# cpu2_lock.net
KiCad netlist of a schematic drawn in Altium Designer
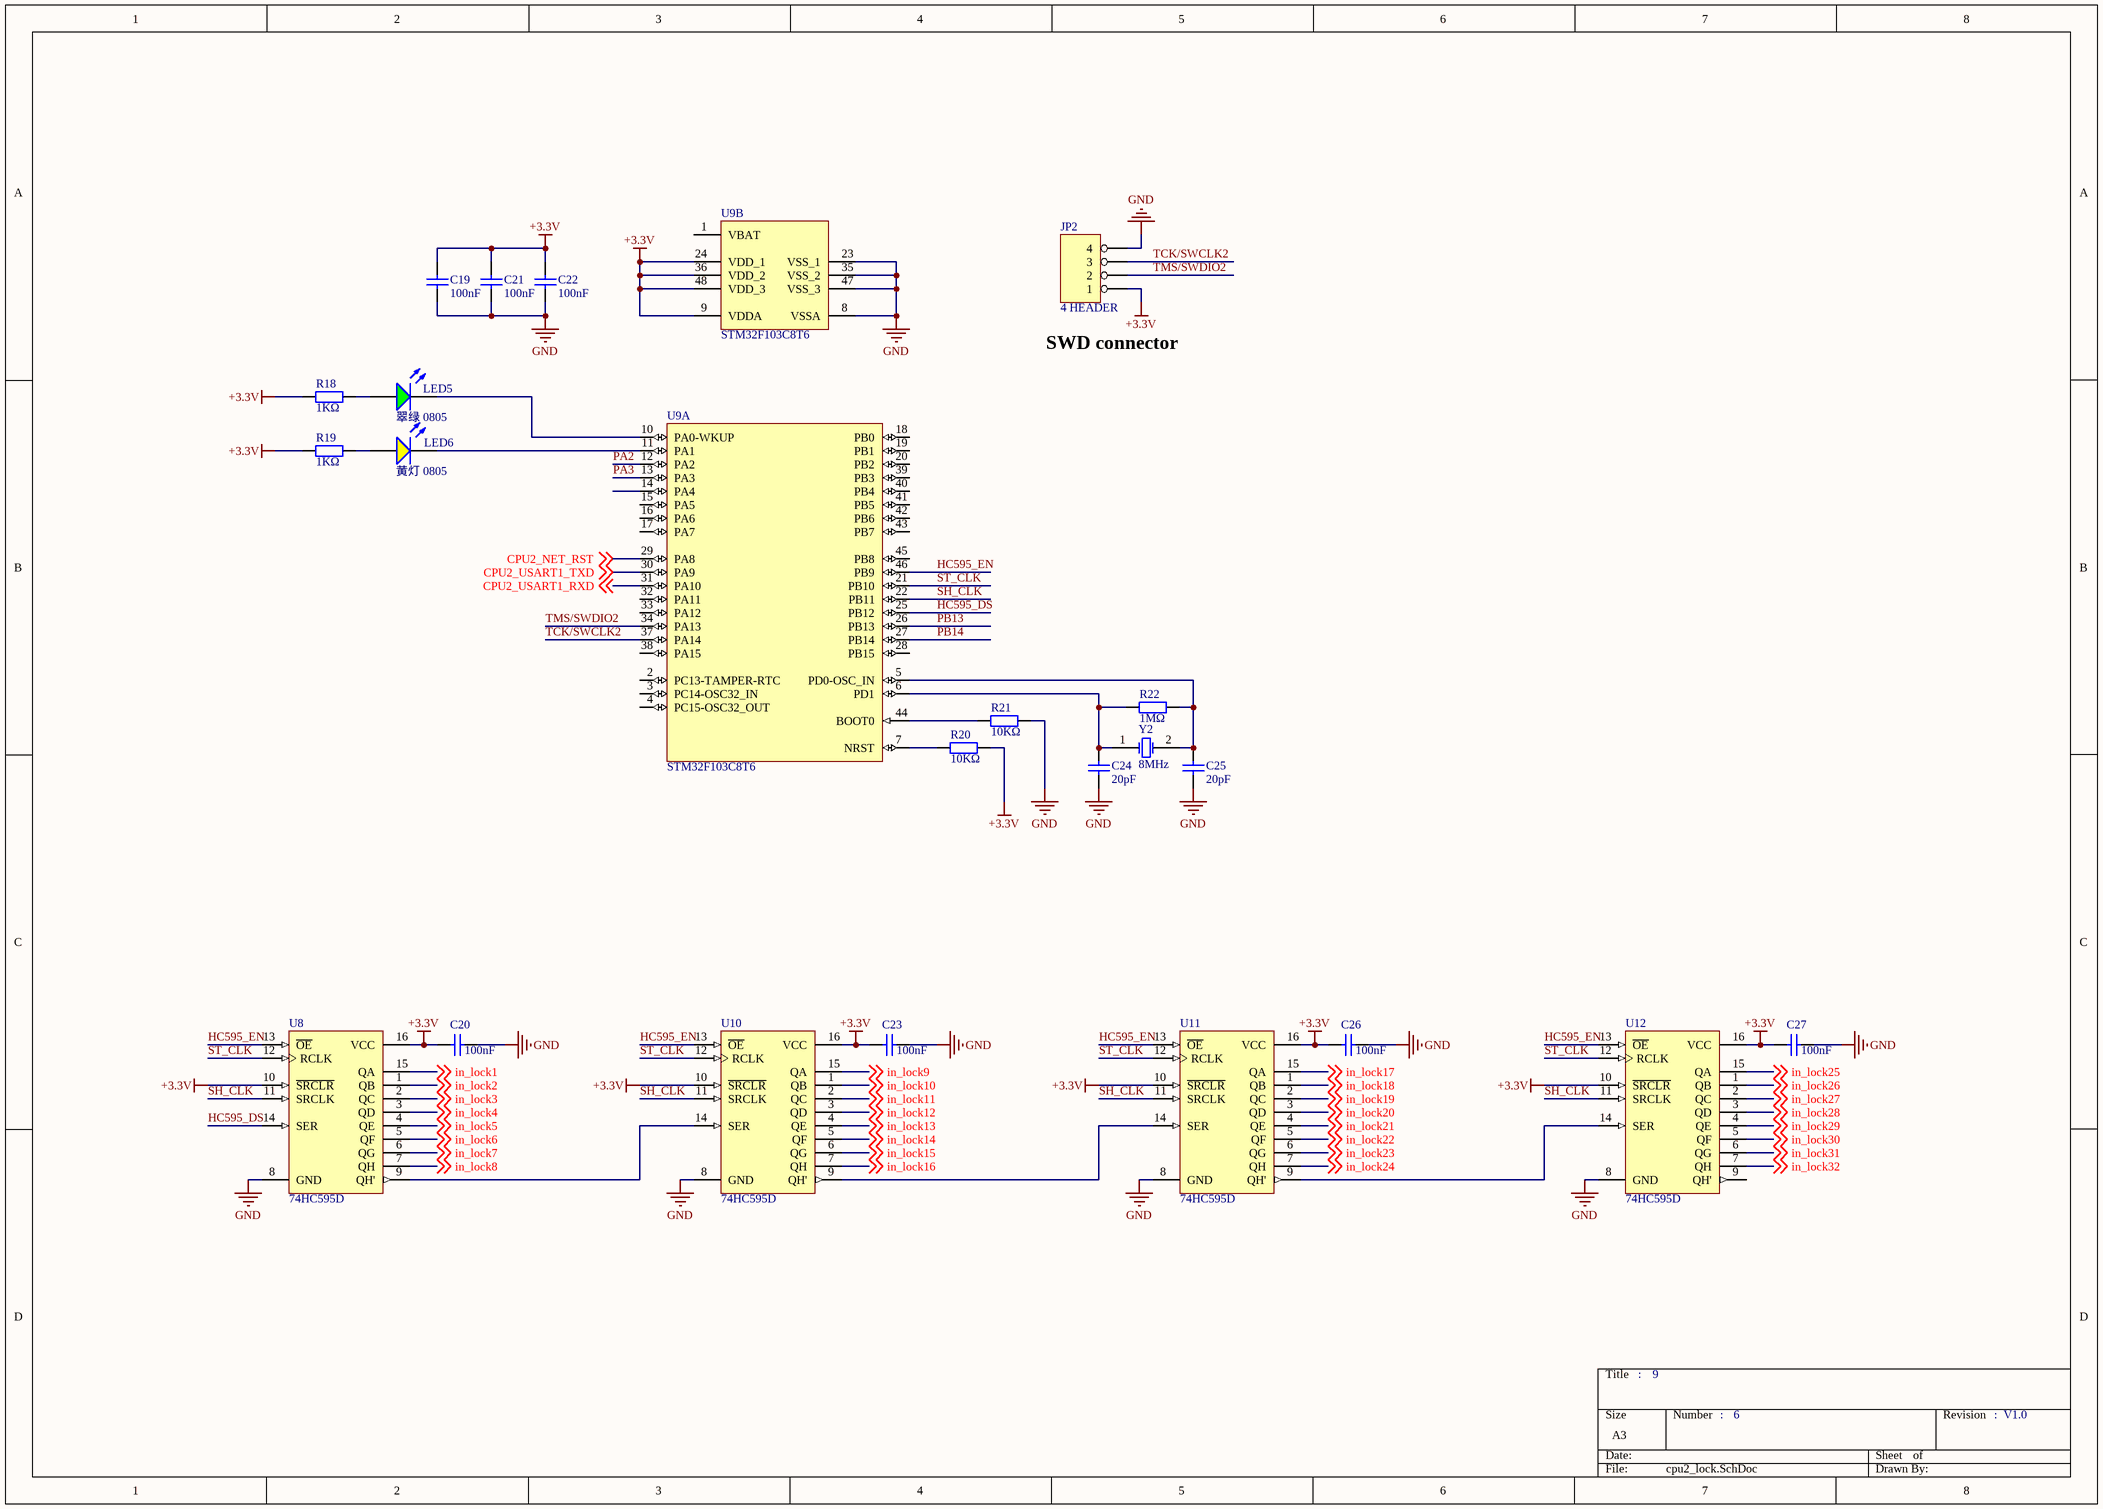
[diagram p0: cpu2_lock.SchDoc]

(export (version "E")
  (design (tool "Eeschema 10.0.6"))
  (components
    (comp (ref "C19")
      (value "100nF")
      (footprint "0805_C")
      (description "贴片电容")
      (libsource (lib "Miscellaneous Devices LC") (part "0805 100nF(104) 10% 50V"))
    )
    (comp (ref "C20")
      (value "100nF")
      (footprint "0805_C")
      (description "贴片电容")
      (libsource (lib "Miscellaneous Devices LC") (part "0805 100nF(104) 10% 50V"))
    )
    (comp (ref "C21")
      (value "100nF")
      (footprint "0805_C")
      (description "贴片电容")
      (libsource (lib "Miscellaneous Devices LC") (part "0805 100nF(104) 10% 50V"))
    )
    (comp (ref "C22")
      (value "100nF")
      (footprint "0805_C")
      (description "贴片电容")
      (libsource (lib "Miscellaneous Devices LC") (part "0805 100nF(104) 10% 50V"))
    )
    (comp (ref "C23")
      (value "100nF")
      (footprint "0805_C")
      (description "贴片电容")
      (libsource (lib "Miscellaneous Devices LC") (part "0805 100nF(104) 10% 50V"))
    )
    (comp (ref "C24")
      (value "20pF")
      (footprint "0805_C")
      (description "贴片电容")
      (libsource (lib "Miscellaneous Devices LC") (part "0805 100nF(104) 10% 50V"))
    )
    (comp (ref "C25")
      (value "20pF")
      (footprint "0805_C")
      (description "贴片电容")
      (libsource (lib "Miscellaneous Devices LC") (part "0805 100nF(104) 10% 50V"))
    )
    (comp (ref "C26")
      (value "100nF")
      (footprint "0805_C")
      (description "贴片电容")
      (libsource (lib "Miscellaneous Devices LC") (part "0805 100nF(104) 10% 50V"))
    )
    (comp (ref "C27")
      (value "100nF")
      (footprint "0805_C")
      (description "贴片电容")
      (libsource (lib "Miscellaneous Devices LC") (part "0805 100nF(104) 10% 50V"))
    )
    (comp (ref "JP2")
      (value "4 HEADER")
      (footprint "CON4_1.5")
      (description "4 Pin Header")
      (libsource (lib "Miscellaneous Devices") (part "4 HEADER"))
    )
    (comp (ref "LED5")
      (value "翠绿 0805")
      (footprint "0805_LED_S1")
      (description "发光二极管")
      (libsource (lib "Miscellaneous Devices LC") (part "0805 翠绿"))
    )
    (comp (ref "LED6")
      (value "黄灯 0805")
      (footprint "0805_LED_S1")
      (description "发光二极管")
      (libsource (lib "Miscellaneous Devices LC") (part "0805 黄灯"))
    )
    (comp (ref "R18")
      (value "1KΩ")
      (footprint "0805_R")
      (description "贴片电阻")
      (libsource (lib "Miscellaneous Devices LC") (part "0805 11KΩ (1102) 1%"))
    )
    (comp (ref "R19")
      (value "1KΩ")
      (footprint "0805_R")
      (description "贴片电阻")
      (libsource (lib "Miscellaneous Devices LC") (part "0805 11KΩ (1102) 1%"))
    )
    (comp (ref "R20")
      (value "10KΩ")
      (footprint "0805_R")
      (description "贴片电阻")
      (libsource (lib "") (part "0805 11KΩ (1102) 1%_1"))
    )
    (comp (ref "R21")
      (value "10KΩ")
      (footprint "0805_R")
      (description "贴片电阻")
      (libsource (lib "") (part "0805 11KΩ (1102) 1%_1"))
    )
    (comp (ref "R22")
      (value "1MΩ")
      (footprint "0805_R")
      (description "贴片电阻")
      (libsource (lib "") (part "0805 11KΩ (1102) 1%_1"))
    )
    (comp (ref "U8")
      (value "74HC595D")
      (footprint "SOIC-16_150mil")
      (description "74系列逻辑芯片")
      (libsource (lib "Miscellaneous Devices LC") (part "74HC595D"))
    )
    (comp (ref "U9")
      (value "STM32F103C8T6")
      (footprint "LQFP-48_7x7x05P")
      (description "ARM")
      (libsource (lib "Miscellaneous Devices LC") (part "STM32F103C8T6"))
    )
    (comp (ref "U10")
      (value "74HC595D")
      (footprint "SOIC-16_150mil")
      (description "74系列逻辑芯片")
      (libsource (lib "Miscellaneous Devices LC") (part "74HC595D"))
    )
    (comp (ref "U11")
      (value "74HC595D")
      (footprint "SOIC-16_150mil")
      (description "74系列逻辑芯片")
      (libsource (lib "Miscellaneous Devices LC") (part "74HC595D"))
    )
    (comp (ref "U12")
      (value "74HC595D")
      (footprint "SOIC-16_150mil")
      (description "74系列逻辑芯片")
      (libsource (lib "Miscellaneous Devices LC") (part "74HC595D"))
    )
    (comp (ref "Y2")
      (value "8MHz")
      (footprint "XTAL_US1")
      (description "Crystal Oscillator")
      (fields (field (name "PUBLISHER") "Altium Limited"))
      (libsource (lib "战舰STM32开发板底板封装库") (part "XTAL"))
    )
  )
  (nets
    (net (code "1") (name "+3.3V") (class "Default")
      (node (ref "C19") (pin "2") (pinfunction "2_2") (pintype "passive"))
      (node (ref "C20") (pin "2") (pinfunction "2_2") (pintype "passive"))
      (node (ref "C21") (pin "2") (pinfunction "2_2") (pintype "passive"))
      (node (ref "C22") (pin "2") (pinfunction "2_2") (pintype "passive"))
      (node (ref "C23") (pin "2") (pinfunction "2_2") (pintype "passive"))
      (node (ref "C26") (pin "2") (pinfunction "2_2") (pintype "passive"))
      (node (ref "C27") (pin "2") (pinfunction "2_2") (pintype "passive"))
      (node (ref "JP2") (pin "1") (pinfunction "1_1") (pintype "passive"))
      (node (ref "R18") (pin "1") (pinfunction "1_1") (pintype "passive"))
      (node (ref "R19") (pin "1") (pinfunction "1_1") (pintype "passive"))
      (node (ref "R20") (pin "1") (pinfunction "1_1") (pintype "passive"))
      (node (ref "U10") (pin "10") (pinfunction "~{SRCLR}_10") (pintype "input"))
      (node (ref "U10") (pin "16") (pinfunction "VCC_16") (pintype "power_in"))
      (node (ref "U11") (pin "10") (pinfunction "~{SRCLR}_10") (pintype "input"))
      (node (ref "U11") (pin "16") (pinfunction "VCC_16") (pintype "power_in"))
      (node (ref "U12") (pin "10") (pinfunction "~{SRCLR}_10") (pintype "input"))
      (node (ref "U12") (pin "16") (pinfunction "VCC_16") (pintype "power_in"))
      (node (ref "U8") (pin "10") (pinfunction "~{SRCLR}_10") (pintype "input"))
      (node (ref "U8") (pin "16") (pinfunction "VCC_16") (pintype "power_in"))
      (node (ref "U9") (pin "24") (pinfunction "VDD_1_24") (pintype "power_in"))
      (node (ref "U9") (pin "36") (pinfunction "VDD_2_36") (pintype "power_in"))
      (node (ref "U9") (pin "48") (pinfunction "VDD_3_48") (pintype "power_in"))
      (node (ref "U9") (pin "9") (pinfunction "VDDA_9") (pintype "power_in"))
    )
    (net (code "2") (name "/HC595_DS") (class "Default")
      (node (ref "U8") (pin "14") (pinfunction "SER_14") (pintype "input"))
      (node (ref "U9") (pin "25") (pinfunction "PB12_25") (pintype "bidirectional"))
    )
    (net (code "3") (name "/HC595_EN") (class "Default")
      (node (ref "U10") (pin "13") (pinfunction "~{OE}_13") (pintype "input"))
      (node (ref "U11") (pin "13") (pinfunction "~{OE}_13") (pintype "input"))
      (node (ref "U12") (pin "13") (pinfunction "~{OE}_13") (pintype "input"))
      (node (ref "U8") (pin "13") (pinfunction "~{OE}_13") (pintype "input"))
      (node (ref "U9") (pin "46") (pinfunction "PB9_46") (pintype "bidirectional"))
    )
    (net (code "4") (name "/PA2") (class "Default")
      (node (ref "U9") (pin "12") (pinfunction "PA2_12") (pintype "bidirectional"))
    )
    (net (code "5") (name "/PA3") (class "Default")
      (node (ref "U9") (pin "13") (pinfunction "PA3_13") (pintype "bidirectional"))
    )
    (net (code "6") (name "/PB13") (class "Default")
      (node (ref "U9") (pin "26") (pinfunction "PB13_26") (pintype "bidirectional"))
    )
    (net (code "7") (name "/PB14") (class "Default")
      (node (ref "U9") (pin "27") (pinfunction "PB14_27") (pintype "bidirectional"))
    )
    (net (code "8") (name "/SH_CLK") (class "Default")
      (node (ref "U10") (pin "11") (pinfunction "SRCLK_11") (pintype "input"))
      (node (ref "U11") (pin "11") (pinfunction "SRCLK_11") (pintype "input"))
      (node (ref "U12") (pin "11") (pinfunction "SRCLK_11") (pintype "input"))
      (node (ref "U8") (pin "11") (pinfunction "SRCLK_11") (pintype "input"))
      (node (ref "U9") (pin "22") (pinfunction "PB11_22") (pintype "bidirectional"))
    )
    (net (code "9") (name "/ST_CLK") (class "Default")
      (node (ref "U10") (pin "12") (pinfunction "RCLK_12") (pintype "input"))
      (node (ref "U11") (pin "12") (pinfunction "RCLK_12") (pintype "input"))
      (node (ref "U12") (pin "12") (pinfunction "RCLK_12") (pintype "input"))
      (node (ref "U8") (pin "12") (pinfunction "RCLK_12") (pintype "input"))
      (node (ref "U9") (pin "21") (pinfunction "PB10_21") (pintype "bidirectional"))
    )
    (net (code "10") (name "/TCK{slash}SWCLK2") (class "Default")
      (node (ref "JP2") (pin "3") (pinfunction "3_3") (pintype "passive"))
      (node (ref "U9") (pin "37") (pinfunction "PA14_37") (pintype "bidirectional"))
    )
    (net (code "11") (name "/TMS{slash}SWDIO2") (class "Default")
      (node (ref "JP2") (pin "2") (pinfunction "2_2") (pintype "passive"))
      (node (ref "U9") (pin "34") (pinfunction "PA13_34") (pintype "bidirectional"))
    )
    (net (code "12") (name "CPU2_NET_RST") (class "Default")
      (node (ref "U9") (pin "29") (pinfunction "PA8_29") (pintype "bidirectional"))
    )
    (net (code "13") (name "CPU2_USART1_RXD") (class "Default")
      (node (ref "U9") (pin "31") (pinfunction "PA10_31") (pintype "bidirectional"))
    )
    (net (code "14") (name "CPU2_USART1_TXD") (class "Default")
      (node (ref "U9") (pin "30") (pinfunction "PA9_30") (pintype "bidirectional"))
    )
    (net (code "15") (name "GND") (class "Default")
      (node (ref "C19") (pin "1") (pinfunction "1_1") (pintype "passive"))
      (node (ref "C20") (pin "1") (pinfunction "1_1") (pintype "passive"))
      (node (ref "C21") (pin "1") (pinfunction "1_1") (pintype "passive"))
      (node (ref "C22") (pin "1") (pinfunction "1_1") (pintype "passive"))
      (node (ref "C23") (pin "1") (pinfunction "1_1") (pintype "passive"))
      (node (ref "C24") (pin "1") (pinfunction "1_1") (pintype "passive"))
      (node (ref "C25") (pin "1") (pinfunction "1_1") (pintype "passive"))
      (node (ref "C26") (pin "1") (pinfunction "1_1") (pintype "passive"))
      (node (ref "C27") (pin "1") (pinfunction "1_1") (pintype "passive"))
      (node (ref "JP2") (pin "4") (pinfunction "4_4") (pintype "passive"))
      (node (ref "R21") (pin "1") (pinfunction "1_1") (pintype "passive"))
      (node (ref "U10") (pin "8") (pinfunction "GND_8") (pintype "power_in"))
      (node (ref "U11") (pin "8") (pinfunction "GND_8") (pintype "power_in"))
      (node (ref "U12") (pin "8") (pinfunction "GND_8") (pintype "power_in"))
      (node (ref "U8") (pin "8") (pinfunction "GND_8") (pintype "power_in"))
      (node (ref "U9") (pin "23") (pinfunction "VSS_1_23") (pintype "power_in"))
      (node (ref "U9") (pin "35") (pinfunction "VSS_2_35") (pintype "power_in"))
      (node (ref "U9") (pin "47") (pinfunction "VSS_3_47") (pintype "power_in"))
      (node (ref "U9") (pin "8") (pinfunction "VSSA_8") (pintype "power_in"))
    )
    (net (code "16") (name "Net-(LED5-PadA)") (class "Default")
      (node (ref "LED5") (pin "A") (pinfunction "A_A") (pintype "passive"))
      (node (ref "R18") (pin "2") (pinfunction "2_2") (pintype "passive"))
    )
    (net (code "17") (name "Net-(LED6-PadA)") (class "Default")
      (node (ref "LED6") (pin "A") (pinfunction "A_A") (pintype "passive"))
      (node (ref "R19") (pin "2") (pinfunction "2_2") (pintype "passive"))
    )
    (net (code "18") (name "Net-(U9A-BOOT0)") (class "Default")
      (node (ref "R21") (pin "2") (pinfunction "2_2") (pintype "passive"))
      (node (ref "U9") (pin "44") (pinfunction "BOOT0_44") (pintype "input"))
    )
    (net (code "19") (name "Net-(U9A-NRST)") (class "Default")
      (node (ref "R20") (pin "2") (pinfunction "2_2") (pintype "passive"))
      (node (ref "U9") (pin "7") (pinfunction "NRST_7") (pintype "bidirectional"))
    )
    (net (code "20") (name "Net-(U9A-PA0-WKUP)") (class "Default")
      (node (ref "LED5") (pin "K") (pinfunction "K_K") (pintype "passive"))
      (node (ref "U9") (pin "10") (pinfunction "PA0-WKUP_10") (pintype "bidirectional"))
    )
    (net (code "21") (name "Net-(U9A-PA1)") (class "Default")
      (node (ref "LED6") (pin "K") (pinfunction "K_K") (pintype "passive"))
      (node (ref "U9") (pin "11") (pinfunction "PA1_11") (pintype "bidirectional"))
    )
    (net (code "22") (name "Net-(U9A-PD0-OSC_IN)") (class "Default")
      (node (ref "C25") (pin "2") (pinfunction "2_2") (pintype "passive"))
      (node (ref "R22") (pin "1") (pinfunction "1_1") (pintype "passive"))
      (node (ref "U9") (pin "5") (pinfunction "PD0-OSC_IN_5") (pintype "bidirectional"))
      (node (ref "Y2") (pin "2") (pinfunction "OSC2_2") (pintype "passive"))
    )
    (net (code "23") (name "Net-(U9A-PD1)") (class "Default")
      (node (ref "C24") (pin "2") (pinfunction "2_2") (pintype "passive"))
      (node (ref "R22") (pin "2") (pinfunction "2_2") (pintype "passive"))
      (node (ref "U9") (pin "6") (pinfunction "PD1_6") (pintype "bidirectional"))
      (node (ref "Y2") (pin "1") (pinfunction "OSC1_1") (pintype "passive"))
    )
    (net (code "24") (name "Net-(U10-QH')") (class "Default")
      (node (ref "U10") (pin "9") (pinfunction "QH'_9") (pintype "output"))
      (node (ref "U11") (pin "14") (pinfunction "SER_14") (pintype "input"))
    )
    (net (code "25") (name "Net-(U10-SER)") (class "Default")
      (node (ref "U10") (pin "14") (pinfunction "SER_14") (pintype "input"))
      (node (ref "U8") (pin "9") (pinfunction "QH'_9") (pintype "output"))
    )
    (net (code "26") (name "Net-(U11-QH')") (class "Default")
      (node (ref "U11") (pin "9") (pinfunction "QH'_9") (pintype "output"))
      (node (ref "U12") (pin "14") (pinfunction "SER_14") (pintype "input"))
    )
    (net (code "27") (name "in_lock1") (class "Default")
      (node (ref "U8") (pin "15") (pinfunction "QA_15") (pintype "tri_state"))
    )
    (net (code "28") (name "in_lock2") (class "Default")
      (node (ref "U8") (pin "1") (pinfunction "QB_1") (pintype "tri_state"))
    )
    (net (code "29") (name "in_lock3") (class "Default")
      (node (ref "U8") (pin "2") (pinfunction "QC_2") (pintype "tri_state"))
    )
    (net (code "30") (name "in_lock4") (class "Default")
      (node (ref "U8") (pin "3") (pinfunction "QD_3") (pintype "tri_state"))
    )
    (net (code "31") (name "in_lock5") (class "Default")
      (node (ref "U8") (pin "4") (pinfunction "QE_4") (pintype "tri_state"))
    )
    (net (code "32") (name "in_lock6") (class "Default")
      (node (ref "U8") (pin "5") (pinfunction "QF_5") (pintype "tri_state"))
    )
    (net (code "33") (name "in_lock7") (class "Default")
      (node (ref "U8") (pin "6") (pinfunction "QG_6") (pintype "tri_state"))
    )
    (net (code "34") (name "in_lock8") (class "Default")
      (node (ref "U8") (pin "7") (pinfunction "QH_7") (pintype "tri_state"))
    )
    (net (code "35") (name "in_lock9") (class "Default")
      (node (ref "U10") (pin "15") (pinfunction "QA_15") (pintype "tri_state"))
    )
    (net (code "36") (name "in_lock10") (class "Default")
      (node (ref "U10") (pin "1") (pinfunction "QB_1") (pintype "tri_state"))
    )
    (net (code "37") (name "in_lock11") (class "Default")
      (node (ref "U10") (pin "2") (pinfunction "QC_2") (pintype "tri_state"))
    )
    (net (code "38") (name "in_lock12") (class "Default")
      (node (ref "U10") (pin "3") (pinfunction "QD_3") (pintype "tri_state"))
    )
    (net (code "39") (name "in_lock13") (class "Default")
      (node (ref "U10") (pin "4") (pinfunction "QE_4") (pintype "tri_state"))
    )
    (net (code "40") (name "in_lock14") (class "Default")
      (node (ref "U10") (pin "5") (pinfunction "QF_5") (pintype "tri_state"))
    )
    (net (code "41") (name "in_lock15") (class "Default")
      (node (ref "U10") (pin "6") (pinfunction "QG_6") (pintype "tri_state"))
    )
    (net (code "42") (name "in_lock16") (class "Default")
      (node (ref "U10") (pin "7") (pinfunction "QH_7") (pintype "tri_state"))
    )
    (net (code "43") (name "in_lock17") (class "Default")
      (node (ref "U11") (pin "15") (pinfunction "QA_15") (pintype "tri_state"))
    )
    (net (code "44") (name "in_lock18") (class "Default")
      (node (ref "U11") (pin "1") (pinfunction "QB_1") (pintype "tri_state"))
    )
    (net (code "45") (name "in_lock19") (class "Default")
      (node (ref "U11") (pin "2") (pinfunction "QC_2") (pintype "tri_state"))
    )
    (net (code "46") (name "in_lock20") (class "Default")
      (node (ref "U11") (pin "3") (pinfunction "QD_3") (pintype "tri_state"))
    )
    (net (code "47") (name "in_lock21") (class "Default")
      (node (ref "U11") (pin "4") (pinfunction "QE_4") (pintype "tri_state"))
    )
    (net (code "48") (name "in_lock22") (class "Default")
      (node (ref "U11") (pin "5") (pinfunction "QF_5") (pintype "tri_state"))
    )
    (net (code "49") (name "in_lock23") (class "Default")
      (node (ref "U11") (pin "6") (pinfunction "QG_6") (pintype "tri_state"))
    )
    (net (code "50") (name "in_lock24") (class "Default")
      (node (ref "U11") (pin "7") (pinfunction "QH_7") (pintype "tri_state"))
    )
    (net (code "51") (name "in_lock25") (class "Default")
      (node (ref "U12") (pin "15") (pinfunction "QA_15") (pintype "tri_state"))
    )
    (net (code "52") (name "in_lock26") (class "Default")
      (node (ref "U12") (pin "1") (pinfunction "QB_1") (pintype "tri_state"))
    )
    (net (code "53") (name "in_lock27") (class "Default")
      (node (ref "U12") (pin "2") (pinfunction "QC_2") (pintype "tri_state"))
    )
    (net (code "54") (name "in_lock28") (class "Default")
      (node (ref "U12") (pin "3") (pinfunction "QD_3") (pintype "tri_state"))
    )
    (net (code "55") (name "in_lock29") (class "Default")
      (node (ref "U12") (pin "4") (pinfunction "QE_4") (pintype "tri_state"))
    )
    (net (code "56") (name "in_lock30") (class "Default")
      (node (ref "U12") (pin "5") (pinfunction "QF_5") (pintype "tri_state"))
    )
    (net (code "57") (name "in_lock31") (class "Default")
      (node (ref "U12") (pin "6") (pinfunction "QG_6") (pintype "tri_state"))
    )
    (net (code "58") (name "in_lock32") (class "Default")
      (node (ref "U12") (pin "7") (pinfunction "QH_7") (pintype "tri_state"))
    )
    (net (code "59") (name "unconnected-(U9A-PA4-Pad14)") (class "Default")
      (node (ref "U9") (pin "14") (pinfunction "PA4_14") (pintype "bidirectional"))
    )
    (net (code "60") (name "unconnected-(U9A-PA5-Pad15)") (class "Default")
      (node (ref "U9") (pin "15") (pinfunction "PA5_15") (pintype "bidirectional"))
    )
    (net (code "61") (name "unconnected-(U9A-PA6-Pad16)") (class "Default")
      (node (ref "U9") (pin "16") (pinfunction "PA6_16") (pintype "bidirectional"))
    )
    (net (code "62") (name "unconnected-(U9A-PA7-Pad17)") (class "Default")
      (node (ref "U9") (pin "17") (pinfunction "PA7_17") (pintype "bidirectional"))
    )
    (net (code "63") (name "unconnected-(U9A-PA11-Pad32)") (class "Default")
      (node (ref "U9") (pin "32") (pinfunction "PA11_32") (pintype "bidirectional"))
    )
    (net (code "64") (name "unconnected-(U9A-PA12-Pad33)") (class "Default")
      (node (ref "U9") (pin "33") (pinfunction "PA12_33") (pintype "bidirectional"))
    )
    (net (code "65") (name "unconnected-(U9A-PA15-Pad38)") (class "Default")
      (node (ref "U9") (pin "38") (pinfunction "PA15_38") (pintype "bidirectional"))
    )
    (net (code "66") (name "unconnected-(U9A-PB0-Pad18)") (class "Default")
      (node (ref "U9") (pin "18") (pinfunction "PB0_18") (pintype "bidirectional"))
    )
    (net (code "67") (name "unconnected-(U9A-PB1-Pad19)") (class "Default")
      (node (ref "U9") (pin "19") (pinfunction "PB1_19") (pintype "bidirectional"))
    )
    (net (code "68") (name "unconnected-(U9A-PB2-Pad20)") (class "Default")
      (node (ref "U9") (pin "20") (pinfunction "PB2_20") (pintype "bidirectional"))
    )
    (net (code "69") (name "unconnected-(U9A-PB3-Pad39)") (class "Default")
      (node (ref "U9") (pin "39") (pinfunction "PB3_39") (pintype "bidirectional"))
    )
    (net (code "70") (name "unconnected-(U9A-PB4-Pad40)") (class "Default")
      (node (ref "U9") (pin "40") (pinfunction "PB4_40") (pintype "bidirectional"))
    )
    (net (code "71") (name "unconnected-(U9A-PB5-Pad41)") (class "Default")
      (node (ref "U9") (pin "41") (pinfunction "PB5_41") (pintype "bidirectional"))
    )
    (net (code "72") (name "unconnected-(U9A-PB6-Pad42)") (class "Default")
      (node (ref "U9") (pin "42") (pinfunction "PB6_42") (pintype "bidirectional"))
    )
    (net (code "73") (name "unconnected-(U9A-PB7-Pad43)") (class "Default")
      (node (ref "U9") (pin "43") (pinfunction "PB7_43") (pintype "bidirectional"))
    )
    (net (code "74") (name "unconnected-(U9A-PB8-Pad45)") (class "Default")
      (node (ref "U9") (pin "45") (pinfunction "PB8_45") (pintype "bidirectional"))
    )
    (net (code "75") (name "unconnected-(U9A-PB15-Pad28)") (class "Default")
      (node (ref "U9") (pin "28") (pinfunction "PB15_28") (pintype "bidirectional"))
    )
    (net (code "76") (name "unconnected-(U9A-PC13-TAMPER-RTC-Pad2)") (class "Default")
      (node (ref "U9") (pin "2") (pinfunction "PC13-TAMPER-RTC_2") (pintype "bidirectional"))
    )
    (net (code "77") (name "unconnected-(U9A-PC14-OSC32_IN-Pad3)") (class "Default")
      (node (ref "U9") (pin "3") (pinfunction "PC14-OSC32_IN_3") (pintype "bidirectional"))
    )
    (net (code "78") (name "unconnected-(U9A-PC15-OSC32_OUT-Pad4)") (class "Default")
      (node (ref "U9") (pin "4") (pinfunction "PC15-OSC32_OUT_4") (pintype "bidirectional"))
    )
    (net (code "79") (name "unconnected-(U9B-VBAT-Pad1)") (class "Default")
      (node (ref "U9") (pin "1") (pinfunction "VBAT_1") (pintype "power_in"))
    )
    (net (code "80") (name "unconnected-(U12-QH'-Pad9)") (class "Default")
      (node (ref "U12") (pin "9") (pinfunction "QH'_9") (pintype "output"))
    )
  )
)
